# hw2_sch.net
KiCad netlist of a schematic drawn in EAGLE
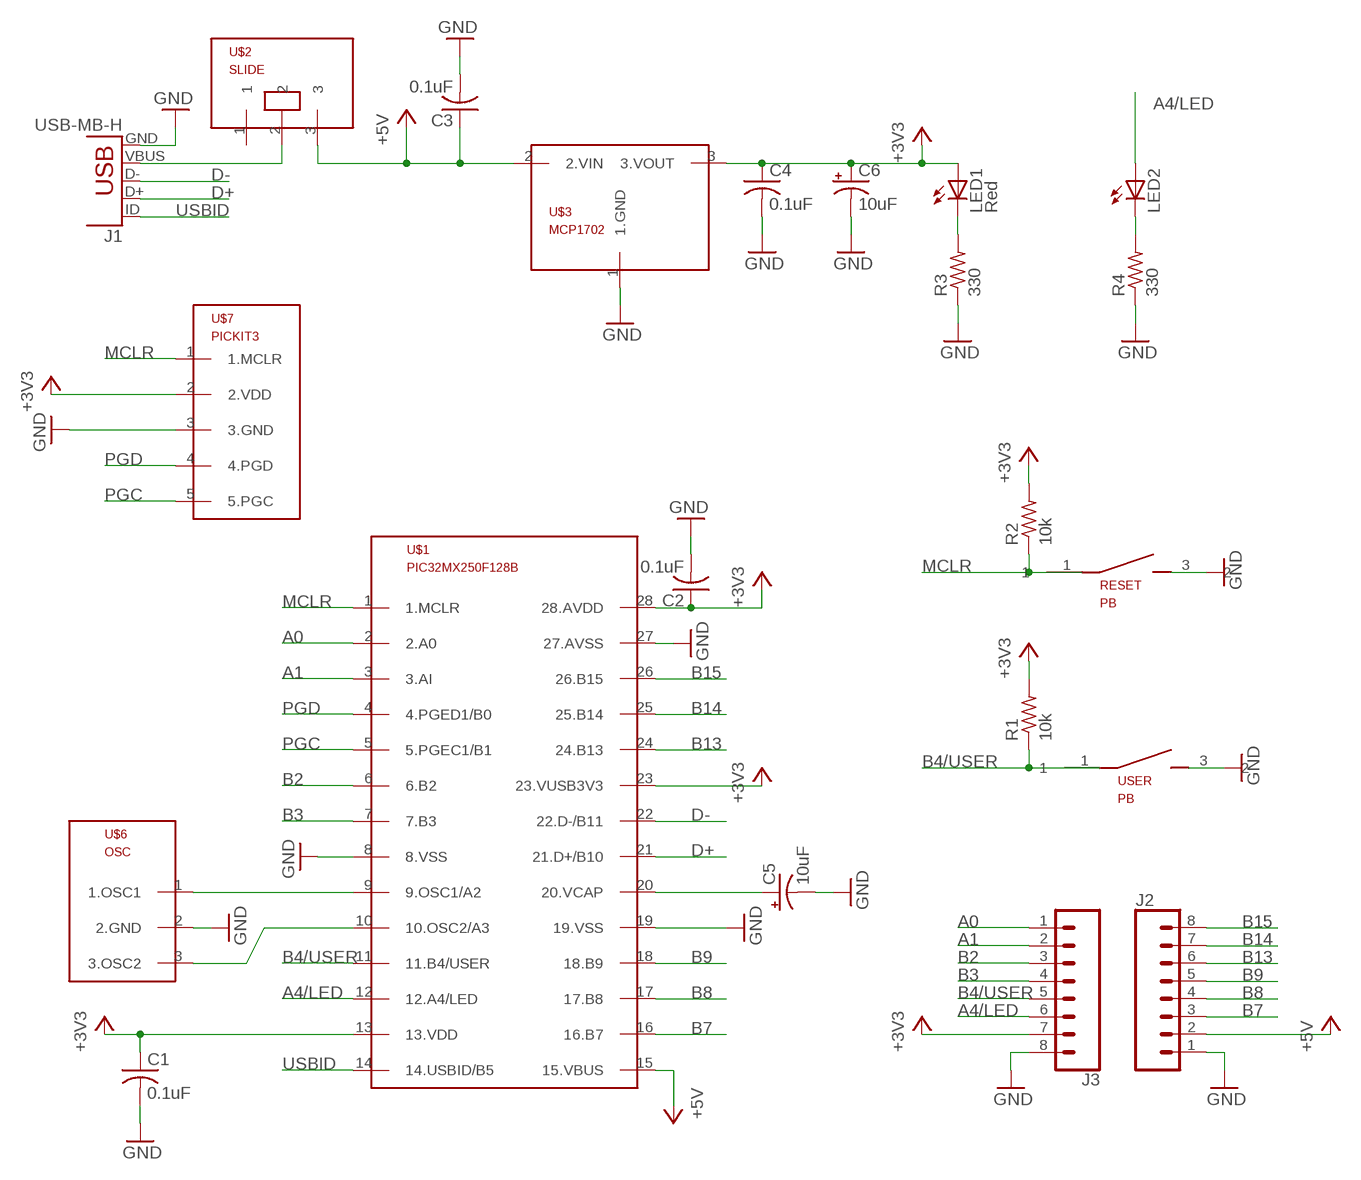
[diagram p0: schematic, sheet 1]

(export (version "E")
  (design (tool "Eeschema 10.0.6"))
  (components
    (comp (ref "C1")
      (value "0.1uF")
      (footprint "eagle-import:C025-025X050")
      (libsource (lib "eagle-import") (part "C-US025-025X050"))
    )
    (comp (ref "C2")
      (value "0.1uF")
      (footprint "eagle-import:C025-025X050")
      (libsource (lib "eagle-import") (part "C-US025-025X050"))
    )
    (comp (ref "C3")
      (value "0.1uF")
      (footprint "eagle-import:C025-025X050")
      (libsource (lib "eagle-import") (part "C-US025-025X050"))
    )
    (comp (ref "C4")
      (value "0.1uF")
      (footprint "eagle-import:C025-025X050")
      (libsource (lib "eagle-import") (part "C-US025-025X050"))
    )
    (comp (ref "C5")
      (value "10uF")
      (footprint "eagle-import:B45181B")
      (libsource (lib "eagle-import") (part "CPOL-USB45181B"))
    )
    (comp (ref "C6")
      (value "10uF")
      (footprint "eagle-import:B45181B")
      (libsource (lib "eagle-import") (part "CPOL-USB45181B"))
    )
    (comp (ref "J1")
      (value "USB-MB-H")
      (footprint "eagle-import:USB-MB-H")
      (libsource (lib "eagle-import") (part "USB-MB-H"))
    )
    (comp (ref "J2")
      (value "CONN_08\"")
      (footprint "eagle-import:1X08")
      (libsource (lib "eagle-import") (part "CONN_08{dblquote}"))
    )
    (comp (ref "J3")
      (value "CONN_08\"")
      (footprint "eagle-import:1X08")
      (libsource (lib "eagle-import") (part "CONN_08{dblquote}"))
    )
    (comp (ref "LED1")
      (value "Red")
      (footprint "eagle-import:LED3MM")
      (libsource (lib "eagle-import") (part "LED3MM"))
    )
    (comp (ref "LED2")
      (value "LED3MM")
      (footprint "eagle-import:LED3MM")
      (libsource (lib "eagle-import") (part "LED3MM"))
    )
    (comp (ref "R1")
      (value "10k")
      (footprint "eagle-import:0207_10")
      (libsource (lib "eagle-import") (part "R-US_0207/10"))
    )
    (comp (ref "R2")
      (value "10k")
      (footprint "eagle-import:0207_10")
      (libsource (lib "eagle-import") (part "R-US_0207/10"))
    )
    (comp (ref "R3")
      (value "330")
      (footprint "eagle-import:0207_10")
      (libsource (lib "eagle-import") (part "R-US_0207/10"))
    )
    (comp (ref "R4")
      (value "330")
      (footprint "eagle-import:0207_10")
      (libsource (lib "eagle-import") (part "R-US_0207/10"))
    )
    (comp (ref "RESET")
      (value "PB")
      (footprint "eagle-import:PB")
      (libsource (lib "eagle-import") (part "PB"))
    )
    (comp (ref "U$1")
      (value "PIC32MX250F128B")
      (footprint "eagle-import:DIL28-3")
      (libsource (lib "eagle-import") (part "PIC32MX250F128B"))
    )
    (comp (ref "U$2")
      (value "SLIDE")
      (footprint "eagle-import:SLIDE")
      (libsource (lib "eagle-import") (part "SLIDE"))
    )
    (comp (ref "U$3")
      (value "MCP1702")
      (footprint "eagle-import:TO92")
      (libsource (lib "eagle-import") (part "MCP1702"))
    )
    (comp (ref "U$6")
      (value "OSC")
      (footprint "eagle-import:OSC")
      (libsource (lib "eagle-import") (part "OSC"))
    )
    (comp (ref "U$7")
      (value "PICKIT3")
      (footprint "eagle-import:1X05")
      (libsource (lib "eagle-import") (part "PICKIT3"))
    )
    (comp (ref "USER")
      (value "PB")
      (footprint "eagle-import:PB")
      (libsource (lib "eagle-import") (part "PB"))
    )
  )
  (nets
    (net (code "1") (name "+3V3") (class "Default")
      (node (ref "C1") (pin "1") (pinfunction "1_1") (pintype "passive"))
      (node (ref "C2") (pin "1") (pinfunction "1_1") (pintype "passive"))
      (node (ref "C4") (pin "1") (pinfunction "1_1") (pintype "passive"))
      (node (ref "C6") (pin "+") (pinfunction "+_+") (pintype "passive"))
      (node (ref "J3") (pin "7") (pinfunction "7_7") (pintype "passive"))
      (node (ref "LED1") (pin "A") (pinfunction "A_A") (pintype "passive"))
      (node (ref "R1") (pin "2") (pinfunction "2_2") (pintype "passive"))
      (node (ref "R2") (pin "2") (pinfunction "2_2") (pintype "passive"))
      (node (ref "U$1") (pin "13") (pinfunction "13.VDD_13") (pintype "bidirectional"))
      (node (ref "U$1") (pin "23") (pinfunction "23.VUSB3V3_23") (pintype "bidirectional"))
      (node (ref "U$1") (pin "28") (pinfunction "28.AVDD_28") (pintype "bidirectional"))
      (node (ref "U$3") (pin "3") (pinfunction "3.VOUT_3") (pintype "bidirectional"))
      (node (ref "U$7") (pin "2") (pinfunction "2.VDD_2") (pintype "bidirectional"))
    )
    (net (code "2") (name "+5V") (class "Default")
      (node (ref "C3") (pin "1") (pinfunction "1_1") (pintype "passive"))
      (node (ref "J2") (pin "2") (pinfunction "2_2") (pintype "passive"))
      (node (ref "U$1") (pin "15") (pinfunction "15.VBUS_15") (pintype "bidirectional"))
      (node (ref "U$2") (pin "3") (pinfunction "3_3") (pintype "bidirectional"))
      (node (ref "U$3") (pin "2") (pinfunction "2.VIN_2") (pintype "bidirectional"))
    )
    (net (code "3") (name "/A0") (class "Default")
      (node (ref "J3") (pin "1") (pinfunction "1_1") (pintype "passive"))
      (node (ref "U$1") (pin "2") (pinfunction "2.A0_2") (pintype "bidirectional"))
    )
    (net (code "4") (name "/A1") (class "Default")
      (node (ref "J3") (pin "2") (pinfunction "2_2") (pintype "passive"))
      (node (ref "U$1") (pin "3") (pinfunction "3.AI_3") (pintype "bidirectional"))
    )
    (net (code "5") (name "/A4{slash}LED") (class "Default")
      (node (ref "J3") (pin "6") (pinfunction "6_6") (pintype "passive"))
      (node (ref "LED2") (pin "A") (pinfunction "A_A") (pintype "passive"))
      (node (ref "U$1") (pin "12") (pinfunction "12.A4/LED_12") (pintype "bidirectional"))
    )
    (net (code "6") (name "/B2") (class "Default")
      (node (ref "J3") (pin "3") (pinfunction "3_3") (pintype "passive"))
      (node (ref "U$1") (pin "6") (pinfunction "6.B2_6") (pintype "bidirectional"))
    )
    (net (code "7") (name "/B3") (class "Default")
      (node (ref "J3") (pin "4") (pinfunction "4_4") (pintype "passive"))
      (node (ref "U$1") (pin "7") (pinfunction "7.B3_7") (pintype "bidirectional"))
    )
    (net (code "8") (name "/B4{slash}USER") (class "Default")
      (node (ref "J3") (pin "5") (pinfunction "5_5") (pintype "passive"))
      (node (ref "R1") (pin "1") (pinfunction "1_1") (pintype "passive"))
      (node (ref "U$1") (pin "11") (pinfunction "11.B4/USER_11") (pintype "bidirectional"))
      (node (ref "USER") (pin "1") (pinfunction "1_1") (pintype "bidirectional"))
    )
    (net (code "9") (name "/B7") (class "Default")
      (node (ref "J2") (pin "3") (pinfunction "3_3") (pintype "passive"))
      (node (ref "U$1") (pin "16") (pinfunction "16.B7_16") (pintype "bidirectional"))
    )
    (net (code "10") (name "/B8") (class "Default")
      (node (ref "J2") (pin "4") (pinfunction "4_4") (pintype "passive"))
      (node (ref "U$1") (pin "17") (pinfunction "17.B8_17") (pintype "bidirectional"))
    )
    (net (code "11") (name "/B9") (class "Default")
      (node (ref "J2") (pin "5") (pinfunction "5_5") (pintype "passive"))
      (node (ref "U$1") (pin "18") (pinfunction "18.B9_18") (pintype "bidirectional"))
    )
    (net (code "12") (name "/B13") (class "Default")
      (node (ref "J2") (pin "6") (pinfunction "6_6") (pintype "passive"))
      (node (ref "U$1") (pin "24") (pinfunction "24.B13_24") (pintype "bidirectional"))
    )
    (net (code "13") (name "/B14") (class "Default")
      (node (ref "J2") (pin "7") (pinfunction "7_7") (pintype "passive"))
      (node (ref "U$1") (pin "25") (pinfunction "25.B14_25") (pintype "bidirectional"))
    )
    (net (code "14") (name "/B15") (class "Default")
      (node (ref "J2") (pin "8") (pinfunction "8_8") (pintype "passive"))
      (node (ref "U$1") (pin "26") (pinfunction "26.B15_26") (pintype "bidirectional"))
    )
    (net (code "15") (name "/D+") (class "Default")
      (node (ref "J1") (pin "D+") (pinfunction "D+_D+") (pintype "bidirectional"))
      (node (ref "U$1") (pin "21") (pinfunction "21.D+/B10_21") (pintype "bidirectional"))
    )
    (net (code "16") (name "/D-") (class "Default")
      (node (ref "J1") (pin "D-") (pinfunction "D-_D-") (pintype "bidirectional"))
      (node (ref "U$1") (pin "22") (pinfunction "22.D-/B11_22") (pintype "bidirectional"))
    )
    (net (code "17") (name "/MCLR") (class "Default")
      (node (ref "R2") (pin "1") (pinfunction "1_1") (pintype "passive"))
      (node (ref "RESET") (pin "1") (pinfunction "1_1") (pintype "bidirectional"))
      (node (ref "U$1") (pin "1") (pinfunction "1.MCLR_1") (pintype "bidirectional"))
      (node (ref "U$7") (pin "1") (pinfunction "1.MCLR_1") (pintype "bidirectional"))
    )
    (net (code "18") (name "/PGC") (class "Default")
      (node (ref "U$1") (pin "5") (pinfunction "5.PGEC1/B1_5") (pintype "bidirectional"))
      (node (ref "U$7") (pin "5") (pinfunction "5.PGC_5") (pintype "bidirectional"))
    )
    (net (code "19") (name "/PGD") (class "Default")
      (node (ref "U$1") (pin "4") (pinfunction "4.PGED1/B0_4") (pintype "bidirectional"))
      (node (ref "U$7") (pin "4") (pinfunction "4.PGD_4") (pintype "bidirectional"))
    )
    (net (code "20") (name "/USBID") (class "Default")
      (node (ref "J1") (pin "ID") (pinfunction "ID_ID") (pintype "bidirectional"))
      (node (ref "U$1") (pin "14") (pinfunction "14.USBID/B5_14") (pintype "bidirectional"))
    )
    (net (code "21") (name "GND") (class "Default")
      (node (ref "C1") (pin "2") (pinfunction "2_2") (pintype "passive"))
      (node (ref "C2") (pin "2") (pinfunction "2_2") (pintype "passive"))
      (node (ref "C3") (pin "2") (pinfunction "2_2") (pintype "passive"))
      (node (ref "C4") (pin "2") (pinfunction "2_2") (pintype "passive"))
      (node (ref "C5") (pin "-") (pinfunction "-_-") (pintype "passive"))
      (node (ref "C6") (pin "-") (pinfunction "-_-") (pintype "passive"))
      (node (ref "J1") (pin "GND") (pinfunction "GND_GND") (pintype "bidirectional"))
      (node (ref "J2") (pin "1") (pinfunction "1_1") (pintype "passive"))
      (node (ref "J3") (pin "8") (pinfunction "8_8") (pintype "passive"))
      (node (ref "R3") (pin "1") (pinfunction "1_1") (pintype "passive"))
      (node (ref "R4") (pin "1") (pinfunction "1_1") (pintype "passive"))
      (node (ref "RESET") (pin "3") (pinfunction "2_3") (pintype "bidirectional"))
      (node (ref "U$1") (pin "19") (pinfunction "19.VSS_19") (pintype "bidirectional"))
      (node (ref "U$1") (pin "27") (pinfunction "27.AVSS_27") (pintype "bidirectional"))
      (node (ref "U$1") (pin "8") (pinfunction "8.VSS_8") (pintype "bidirectional"))
      (node (ref "U$3") (pin "1") (pinfunction "1.GND_1") (pintype "bidirectional"))
      (node (ref "U$6") (pin "2") (pinfunction "2.GND_2") (pintype "bidirectional"))
      (node (ref "U$7") (pin "3") (pinfunction "3.GND_3") (pintype "bidirectional"))
      (node (ref "USER") (pin "3") (pinfunction "2_3") (pintype "bidirectional"))
    )
    (net (code "22") (name "Net-(J1-PadVBUS)") (class "Default")
      (node (ref "J1") (pin "VBUS") (pinfunction "VBUS_VBUS") (pintype "bidirectional"))
      (node (ref "U$2") (pin "2") (pinfunction "2_2") (pintype "bidirectional"))
    )
    (net (code "23") (name "Net-(LED1-C)") (class "Default")
      (node (ref "LED1") (pin "K") (pinfunction "C_K") (pintype "passive"))
      (node (ref "R3") (pin "2") (pinfunction "2_2") (pintype "passive"))
    )
    (net (code "24") (name "Net-(LED2-C)") (class "Default")
      (node (ref "LED2") (pin "K") (pinfunction "C_K") (pintype "passive"))
      (node (ref "R4") (pin "2") (pinfunction "2_2") (pintype "passive"))
    )
    (net (code "25") (name "Net-(U$1-9.OSC1{slash}A2)") (class "Default")
      (node (ref "U$1") (pin "9") (pinfunction "9.OSC1/A2_9") (pintype "bidirectional"))
      (node (ref "U$6") (pin "1") (pinfunction "1.OSC1_1") (pintype "bidirectional"))
    )
    (net (code "26") (name "Net-(U$1-10.OSC2{slash}A3)") (class "Default")
      (node (ref "U$1") (pin "10") (pinfunction "10.OSC2/A3_10") (pintype "bidirectional"))
      (node (ref "U$6") (pin "3") (pinfunction "3.OSC2_3") (pintype "bidirectional"))
    )
    (net (code "27") (name "Net-(U$1-20.VCAP)") (class "Default")
      (node (ref "C5") (pin "+") (pinfunction "+_+") (pintype "passive"))
      (node (ref "U$1") (pin "20") (pinfunction "20.VCAP_20") (pintype "bidirectional"))
    )
    (net (code "28") (name "unconnected-(U$2-Pad1)") (class "Default")
      (node (ref "U$2") (pin "1") (pinfunction "1_1") (pintype "bidirectional"))
    )
  )
)
